# Aux_Lights_Daughter_REV3.net
KiCad netlist of a schematic drawn in Altium Designer
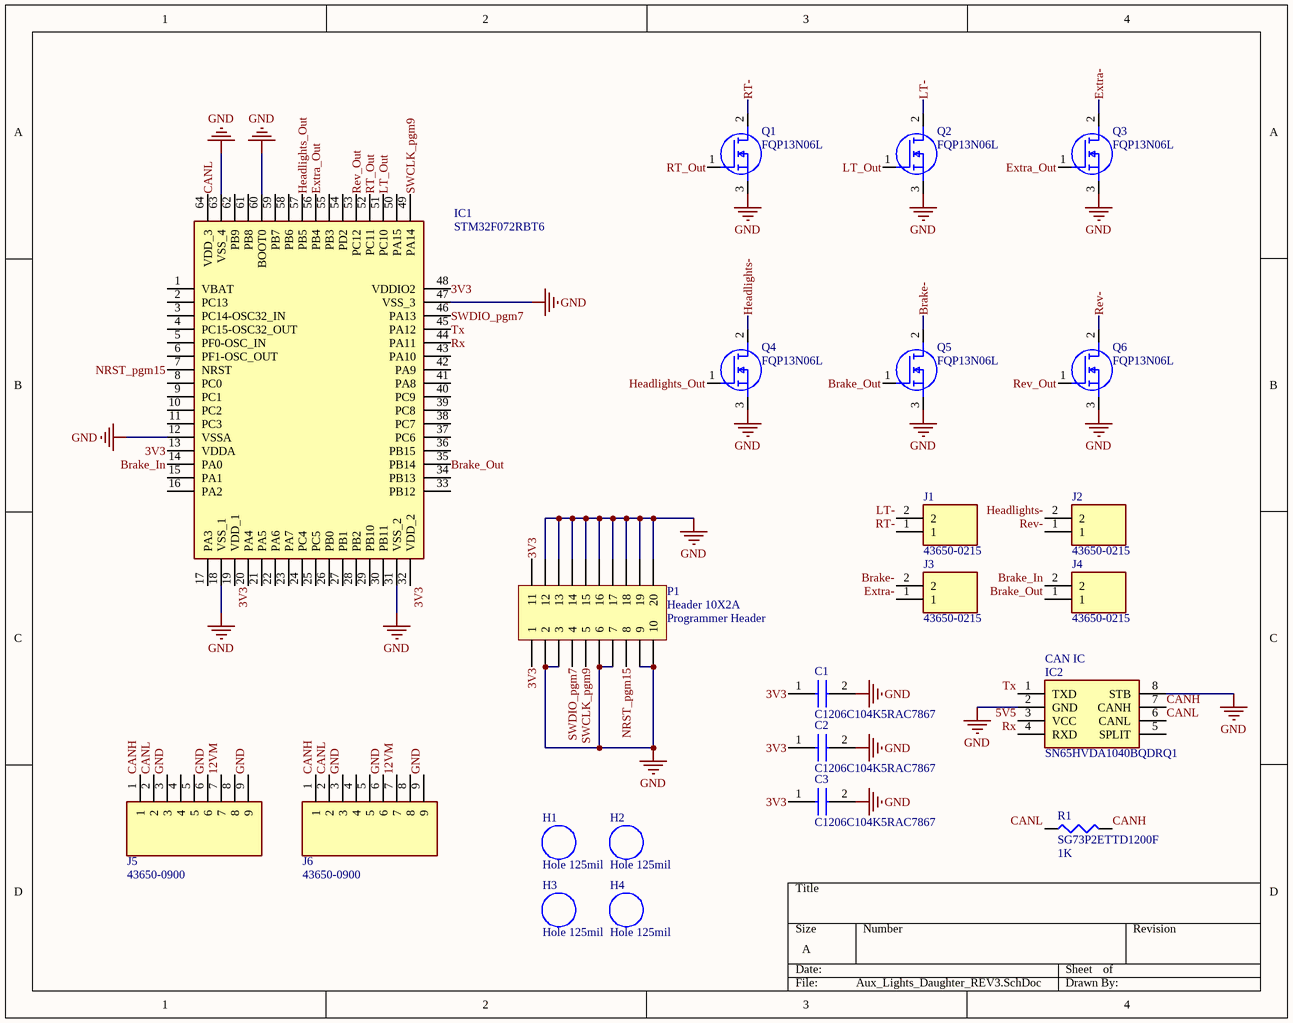
[diagram p0: Aux_Lights_Daughter_REV3.SchDoc]

(export (version "E")
  (design (tool "Eeschema 10.0.6"))
  (components
    (comp (ref "C1")
      (value "C1206C104K5RAC7867")
      (footprint "SG_Common:CAPC3216X110N")
      (description "Capacitor")
      (fields (field (name "MOUSER2 PART NUMBER") "80-C1206104K5RAC7867"))
      (libsource (lib "SG_Common") (part "C1206C104K5RAC7867"))
    )
    (comp (ref "C2")
      (value "C1206C104K5RAC7867")
      (footprint "SG_Common:CAPC3216X110N")
      (description "Capacitor")
      (fields (field (name "MOUSER2 PART NUMBER") "80-C1206104K5RAC7867"))
      (libsource (lib "SG_Common") (part "C1206C104K5RAC7867"))
    )
    (comp (ref "C3")
      (value "C1206C104K5RAC7867")
      (footprint "SG_Common:CAPC3216X110N")
      (description "Capacitor")
      (fields (field (name "MOUSER2 PART NUMBER") "80-C1206104K5RAC7867"))
      (libsource (lib "SG_Common") (part "C1206C104K5RAC7867"))
    )
    (comp (ref "H1")
      (value "Hole 125mil")
      (footprint "Hole")
      (libsource (lib "SG_Common") (part "Hole 125mil"))
    )
    (comp (ref "H2")
      (value "Hole 125mil")
      (footprint "Hole")
      (libsource (lib "SG_Common") (part "Hole 125mil"))
    )
    (comp (ref "H3")
      (value "Hole 125mil")
      (footprint "Hole")
      (libsource (lib "SG_Common") (part "Hole 125mil"))
    )
    (comp (ref "H4")
      (value "Hole 125mil")
      (footprint "Hole")
      (libsource (lib "SG_Common") (part "Hole 125mil"))
    )
    (comp (ref "IC1")
      (value "STM32F072RBT6")
      (footprint "SG_Common:QFP50P1200X1200X160-64N")
      (description "Integrated Circuit")
      (fields (field (name "MOUSER2 PART NUMBER") "511-STM32F072RBT6"))
      (libsource (lib "SG_Common") (part "STM32F072RBT6"))
    )
    (comp (ref "IC2")
      (value "SN65HVDA1040BQDRQ1")
      (footprint "SG_Common:SOIC127P600X175-8N")
      (description "Integrated Circuit")
      (libsource (lib "SG_Common") (part "SN65HVDA1040BQDRQ1"))
    )
    (comp (ref "J1")
      (value "43650-0215")
      (footprint "SG_Common:43650-02YY_15,16,17")
      (description "Connector")
      (fields (field (name "MOUSER2 PART NUMBER") "538-43650-0215"))
      (libsource (lib "SG_Common") (part "43650-0215"))
    )
    (comp (ref "J2")
      (value "43650-0215")
      (footprint "SG_Common:43650-02YY_15,16,17")
      (description "Connector")
      (fields (field (name "MOUSER2 PART NUMBER") "538-43650-0215"))
      (libsource (lib "SG_Common") (part "43650-0215"))
    )
    (comp (ref "J3")
      (value "43650-0215")
      (footprint "SG_Common:43650-02YY_15,16,17")
      (description "Connector")
      (fields (field (name "MOUSER2 PART NUMBER") "538-43650-0215"))
      (libsource (lib "SG_Common") (part "43650-0215"))
    )
    (comp (ref "J4")
      (value "43650-0215")
      (footprint "SG_Common:43650-02YY_15,16,17")
      (description "Connector")
      (fields (field (name "MOUSER2 PART NUMBER") "538-43650-0215"))
      (libsource (lib "SG_Common") (part "43650-0215"))
    )
    (comp (ref "J5")
      (value "43650-0900")
      (footprint "43650-09YY_R")
      (description "Connector")
      (libsource (lib "SG_Common") (part "43650-0900"))
    )
    (comp (ref "J6")
      (value "43650-0900")
      (footprint "43650-09YY_R")
      (description "Connector")
      (libsource (lib "SG_Common") (part "43650-0900"))
    )
    (comp (ref "P1")
      (value "Header 10X2A")
      (footprint "HDR2X10_CEN")
      (description "Header, 10-Pin, Dual row")
      (fields (field (name "PUBLISHER") "Altium Limited"))
      (libsource (lib "Miscellaneous Connectors") (part "Header 10X2A"))
    )
    (comp (ref "Q1")
      (value "FQP13N06L")
      (footprint "SG_Common:TO254P483X1016X2261-3P")
      (description "MOSFET (N-Channel)")
      (fields (field (name "MOUSER2 PART NUMBER") "512-FQP13N06L"))
      (libsource (lib "SG_Common") (part "FQP13N06L"))
    )
    (comp (ref "Q2")
      (value "FQP13N06L")
      (footprint "SG_Common:TO254P483X1016X2261-3P")
      (description "MOSFET (N-Channel)")
      (fields (field (name "MOUSER2 PART NUMBER") "512-FQP13N06L"))
      (libsource (lib "SG_Common") (part "FQP13N06L"))
    )
    (comp (ref "Q3")
      (value "FQP13N06L")
      (footprint "SG_Common:TO254P483X1016X2261-3P")
      (description "MOSFET (N-Channel)")
      (fields (field (name "MOUSER2 PART NUMBER") "512-FQP13N06L"))
      (libsource (lib "SG_Common") (part "FQP13N06L"))
    )
    (comp (ref "Q4")
      (value "FQP13N06L")
      (footprint "SG_Common:TO254P483X1016X2261-3P")
      (description "MOSFET (N-Channel)")
      (fields (field (name "MOUSER2 PART NUMBER") "512-FQP13N06L"))
      (libsource (lib "SG_Common") (part "FQP13N06L"))
    )
    (comp (ref "Q5")
      (value "FQP13N06L")
      (footprint "SG_Common:TO254P483X1016X2261-3P")
      (description "MOSFET (N-Channel)")
      (fields (field (name "MOUSER2 PART NUMBER") "512-FQP13N06L"))
      (libsource (lib "SG_Common") (part "FQP13N06L"))
    )
    (comp (ref "Q6")
      (value "FQP13N06L")
      (footprint "SG_Common:TO254P483X1016X2261-3P")
      (description "MOSFET (N-Channel)")
      (fields (field (name "MOUSER2 PART NUMBER") "512-FQP13N06L"))
      (libsource (lib "SG_Common") (part "FQP13N06L"))
    )
    (comp (ref "R1")
      (value "SG73P2ETTD1200F")
      (footprint "14-1210")
      (description "Resistor")
      (fields (field (name "ALTIUM_VALUE") "1K") (field (name "PUBLISHER") "Altium Limited"))
      (libsource (lib "Miscellaneous Devices") (part "Res3"))
    )
  )
  (nets
    (net (code "1") (name "/3V3") (class "Default")
      (node (ref "C1") (pin "1") (pinfunction "1_1") (pintype "passive"))
      (node (ref "C2") (pin "1") (pinfunction "1_1") (pintype "passive"))
      (node (ref "C3") (pin "1") (pinfunction "1_1") (pintype "passive"))
      (node (ref "IC1") (pin "13") (pinfunction "VDDA_13") (pintype "passive"))
      (node (ref "IC1") (pin "19") (pinfunction "VDD_1_19") (pintype "passive"))
      (node (ref "IC1") (pin "32") (pinfunction "VDD_2_32") (pintype "passive"))
      (node (ref "IC1") (pin "48") (pinfunction "VDDIO2_48") (pintype "passive"))
      (node (ref "P1") (pin "1") (pinfunction "1_1") (pintype "passive"))
      (node (ref "P1") (pin "11") (pinfunction "11_11") (pintype "passive"))
    )
    (net (code "2") (name "/5V5") (class "Default")
      (node (ref "IC2") (pin "3") (pinfunction "VCC_3") (pintype "passive"))
    )
    (net (code "3") (name "/12VM") (class "Default")
      (node (ref "J5") (pin "7") (pinfunction "7_7") (pintype "passive"))
      (node (ref "J6") (pin "7") (pinfunction "7_7") (pintype "passive"))
    )
    (net (code "4") (name "/Brake-") (class "Default")
      (node (ref "J3") (pin "2") (pinfunction "2_2") (pintype "passive"))
      (node (ref "Q5") (pin "2") (pinfunction "D_2") (pintype "passive"))
    )
    (net (code "5") (name "/Brake_In") (class "Default")
      (node (ref "IC1") (pin "14") (pinfunction "PA0_14") (pintype "passive"))
      (node (ref "J4") (pin "2") (pinfunction "2_2") (pintype "passive"))
    )
    (net (code "6") (name "/Brake_Out") (class "Default")
      (node (ref "IC1") (pin "35") (pinfunction "PB14_35") (pintype "passive"))
      (node (ref "J4") (pin "1") (pinfunction "1_1") (pintype "passive"))
      (node (ref "Q5") (pin "1") (pinfunction "G_1") (pintype "passive"))
    )
    (net (code "7") (name "/CANH") (class "Default")
      (node (ref "IC2") (pin "7") (pinfunction "CANH_7") (pintype "passive"))
      (node (ref "J5") (pin "1") (pinfunction "1_1") (pintype "passive"))
      (node (ref "J6") (pin "1") (pinfunction "1_1") (pintype "passive"))
      (node (ref "R1") (pin "2") (pinfunction "2_2") (pintype "passive"))
    )
    (net (code "8") (name "/CANL") (class "Default")
      (node (ref "IC1") (pin "64") (pinfunction "VDD_3_64") (pintype "passive"))
      (node (ref "IC2") (pin "6") (pinfunction "CANL_6") (pintype "passive"))
      (node (ref "J5") (pin "2") (pinfunction "2_2") (pintype "passive"))
      (node (ref "J6") (pin "2") (pinfunction "2_2") (pintype "passive"))
      (node (ref "R1") (pin "1") (pinfunction "1_1") (pintype "passive"))
    )
    (net (code "9") (name "/Extra-") (class "Default")
      (node (ref "J3") (pin "1") (pinfunction "1_1") (pintype "passive"))
      (node (ref "Q3") (pin "2") (pinfunction "D_2") (pintype "passive"))
    )
    (net (code "10") (name "/Extra_Out") (class "Default")
      (node (ref "IC1") (pin "56") (pinfunction "PB4_56") (pintype "passive"))
      (node (ref "Q3") (pin "1") (pinfunction "G_1") (pintype "passive"))
    )
    (net (code "11") (name "/Headlights-") (class "Default")
      (node (ref "J2") (pin "2") (pinfunction "2_2") (pintype "passive"))
      (node (ref "Q4") (pin "2") (pinfunction "D_2") (pintype "passive"))
    )
    (net (code "12") (name "/Headlights_Out") (class "Default")
      (node (ref "IC1") (pin "57") (pinfunction "PB5_57") (pintype "passive"))
      (node (ref "Q4") (pin "1") (pinfunction "G_1") (pintype "passive"))
    )
    (net (code "13") (name "/LT-") (class "Default")
      (node (ref "J1") (pin "2") (pinfunction "2_2") (pintype "passive"))
      (node (ref "Q2") (pin "2") (pinfunction "D_2") (pintype "passive"))
    )
    (net (code "14") (name "/LT_Out") (class "Default")
      (node (ref "IC1") (pin "51") (pinfunction "PC10_51") (pintype "passive"))
      (node (ref "Q2") (pin "1") (pinfunction "G_1") (pintype "passive"))
    )
    (net (code "15") (name "/NRST_pgm15") (class "Default")
      (node (ref "IC1") (pin "7") (pinfunction "NRST_7") (pintype "passive"))
      (node (ref "P1") (pin "8") (pinfunction "8_8") (pintype "passive"))
    )
    (net (code "16") (name "/RT-") (class "Default")
      (node (ref "J1") (pin "1") (pinfunction "1_1") (pintype "passive"))
      (node (ref "Q1") (pin "2") (pinfunction "D_2") (pintype "passive"))
    )
    (net (code "17") (name "/RT_Out") (class "Default")
      (node (ref "IC1") (pin "52") (pinfunction "PC11_52") (pintype "passive"))
      (node (ref "Q1") (pin "1") (pinfunction "G_1") (pintype "passive"))
    )
    (net (code "18") (name "/Rev-") (class "Default")
      (node (ref "J2") (pin "1") (pinfunction "1_1") (pintype "passive"))
      (node (ref "Q6") (pin "2") (pinfunction "D_2") (pintype "passive"))
    )
    (net (code "19") (name "/Rev_Out") (class "Default")
      (node (ref "IC1") (pin "53") (pinfunction "PC12_53") (pintype "passive"))
      (node (ref "Q6") (pin "1") (pinfunction "G_1") (pintype "passive"))
    )
    (net (code "20") (name "/Rx") (class "Default")
      (node (ref "IC1") (pin "44") (pinfunction "PA11_44") (pintype "passive"))
      (node (ref "IC2") (pin "4") (pinfunction "RXD_4") (pintype "passive"))
    )
    (net (code "21") (name "/SWCLK_pgm9") (class "Default")
      (node (ref "IC1") (pin "49") (pinfunction "PA14_49") (pintype "passive"))
      (node (ref "P1") (pin "5") (pinfunction "5_5") (pintype "passive"))
    )
    (net (code "22") (name "/SWDIO_pgm7") (class "Default")
      (node (ref "IC1") (pin "46") (pinfunction "PA13_46") (pintype "passive"))
      (node (ref "P1") (pin "4") (pinfunction "4_4") (pintype "passive"))
    )
    (net (code "23") (name "/Tx") (class "Default")
      (node (ref "IC1") (pin "45") (pinfunction "PA12_45") (pintype "passive"))
      (node (ref "IC2") (pin "1") (pinfunction "TXD_1") (pintype "passive"))
    )
    (net (code "24") (name "GND") (class "Default")
      (node (ref "C1") (pin "2") (pinfunction "2_2") (pintype "passive"))
      (node (ref "C2") (pin "2") (pinfunction "2_2") (pintype "passive"))
      (node (ref "C3") (pin "2") (pinfunction "2_2") (pintype "passive"))
      (node (ref "IC1") (pin "12") (pinfunction "VSSA_12") (pintype "passive"))
      (node (ref "IC1") (pin "18") (pinfunction "VSS_1_18") (pintype "passive"))
      (node (ref "IC1") (pin "31") (pinfunction "VSS_2_31") (pintype "passive"))
      (node (ref "IC1") (pin "47") (pinfunction "VSS_3_47") (pintype "passive"))
      (node (ref "IC1") (pin "60") (pinfunction "BOOT0_60") (pintype "passive"))
      (node (ref "IC1") (pin "63") (pinfunction "VSS_4_63") (pintype "passive"))
      (node (ref "IC2") (pin "2") (pinfunction "GND_2") (pintype "passive"))
      (node (ref "IC2") (pin "8") (pinfunction "STB_8") (pintype "passive"))
      (node (ref "J5") (pin "3") (pinfunction "3_3") (pintype "passive"))
      (node (ref "J5") (pin "6") (pinfunction "6_6") (pintype "passive"))
      (node (ref "J5") (pin "9") (pinfunction "9_9") (pintype "passive"))
      (node (ref "J6") (pin "3") (pinfunction "3_3") (pintype "passive"))
      (node (ref "J6") (pin "6") (pinfunction "6_6") (pintype "passive"))
      (node (ref "J6") (pin "9") (pinfunction "9_9") (pintype "passive"))
      (node (ref "P1") (pin "10") (pinfunction "10_10") (pintype "passive"))
      (node (ref "P1") (pin "12") (pinfunction "12_12") (pintype "passive"))
      (node (ref "P1") (pin "13") (pinfunction "13_13") (pintype "passive"))
      (node (ref "P1") (pin "14") (pinfunction "14_14") (pintype "passive"))
      (node (ref "P1") (pin "15") (pinfunction "15_15") (pintype "passive"))
      (node (ref "P1") (pin "16") (pinfunction "16_16") (pintype "passive"))
      (node (ref "P1") (pin "17") (pinfunction "17_17") (pintype "passive"))
      (node (ref "P1") (pin "18") (pinfunction "18_18") (pintype "passive"))
      (node (ref "P1") (pin "19") (pinfunction "19_19") (pintype "passive"))
      (node (ref "P1") (pin "2") (pinfunction "2_2") (pintype "passive"))
      (node (ref "P1") (pin "20") (pinfunction "20_20") (pintype "passive"))
      (node (ref "P1") (pin "3") (pinfunction "3_3") (pintype "passive"))
      (node (ref "P1") (pin "6") (pinfunction "6_6") (pintype "passive"))
      (node (ref "P1") (pin "7") (pinfunction "7_7") (pintype "passive"))
      (node (ref "P1") (pin "9") (pinfunction "9_9") (pintype "passive"))
      (node (ref "Q1") (pin "3") (pinfunction "S_3") (pintype "passive"))
      (node (ref "Q2") (pin "3") (pinfunction "S_3") (pintype "passive"))
      (node (ref "Q3") (pin "3") (pinfunction "S_3") (pintype "passive"))
      (node (ref "Q4") (pin "3") (pinfunction "S_3") (pintype "passive"))
      (node (ref "Q5") (pin "3") (pinfunction "S_3") (pintype "passive"))
      (node (ref "Q6") (pin "3") (pinfunction "S_3") (pintype "passive"))
    )
    (net (code "25") (name "unconnected-(IC1-PA1-Pad15)") (class "Default")
      (node (ref "IC1") (pin "15") (pinfunction "PA1_15") (pintype "passive"))
    )
    (net (code "26") (name "unconnected-(IC1-PA2-Pad16)") (class "Default")
      (node (ref "IC1") (pin "16") (pinfunction "PA2_16") (pintype "passive"))
    )
    (net (code "27") (name "unconnected-(IC1-PA3-Pad17)") (class "Default")
      (node (ref "IC1") (pin "17") (pinfunction "PA3_17") (pintype "passive"))
    )
    (net (code "28") (name "unconnected-(IC1-PA4-Pad20)") (class "Default")
      (node (ref "IC1") (pin "20") (pinfunction "PA4_20") (pintype "passive"))
    )
    (net (code "29") (name "unconnected-(IC1-PA5-Pad21)") (class "Default")
      (node (ref "IC1") (pin "21") (pinfunction "PA5_21") (pintype "passive"))
    )
    (net (code "30") (name "unconnected-(IC1-PA6-Pad22)") (class "Default")
      (node (ref "IC1") (pin "22") (pinfunction "PA6_22") (pintype "passive"))
    )
    (net (code "31") (name "unconnected-(IC1-PA7-Pad23)") (class "Default")
      (node (ref "IC1") (pin "23") (pinfunction "PA7_23") (pintype "passive"))
    )
    (net (code "32") (name "unconnected-(IC1-PA8-Pad41)") (class "Default")
      (node (ref "IC1") (pin "41") (pinfunction "PA8_41") (pintype "passive"))
    )
    (net (code "33") (name "unconnected-(IC1-PA9-Pad42)") (class "Default")
      (node (ref "IC1") (pin "42") (pinfunction "PA9_42") (pintype "passive"))
    )
    (net (code "34") (name "unconnected-(IC1-PA10-Pad43)") (class "Default")
      (node (ref "IC1") (pin "43") (pinfunction "PA10_43") (pintype "passive"))
    )
    (net (code "35") (name "unconnected-(IC1-PA15-Pad50)") (class "Default")
      (node (ref "IC1") (pin "50") (pinfunction "PA15_50") (pintype "passive"))
    )
    (net (code "36") (name "unconnected-(IC1-PB0-Pad26)") (class "Default")
      (node (ref "IC1") (pin "26") (pinfunction "PB0_26") (pintype "passive"))
    )
    (net (code "37") (name "unconnected-(IC1-PB1-Pad27)") (class "Default")
      (node (ref "IC1") (pin "27") (pinfunction "PB1_27") (pintype "passive"))
    )
    (net (code "38") (name "unconnected-(IC1-PB2-Pad28)") (class "Default")
      (node (ref "IC1") (pin "28") (pinfunction "PB2_28") (pintype "passive"))
    )
    (net (code "39") (name "unconnected-(IC1-PB3-Pad55)") (class "Default")
      (node (ref "IC1") (pin "55") (pinfunction "PB3_55") (pintype "passive"))
    )
    (net (code "40") (name "unconnected-(IC1-PB6-Pad58)") (class "Default")
      (node (ref "IC1") (pin "58") (pinfunction "PB6_58") (pintype "passive"))
    )
    (net (code "41") (name "unconnected-(IC1-PB7-Pad59)") (class "Default")
      (node (ref "IC1") (pin "59") (pinfunction "PB7_59") (pintype "passive"))
    )
    (net (code "42") (name "unconnected-(IC1-PB8-Pad61)") (class "Default")
      (node (ref "IC1") (pin "61") (pinfunction "PB8_61") (pintype "passive"))
    )
    (net (code "43") (name "unconnected-(IC1-PB9-Pad62)") (class "Default")
      (node (ref "IC1") (pin "62") (pinfunction "PB9_62") (pintype "passive"))
    )
    (net (code "44") (name "unconnected-(IC1-PB10-Pad29)") (class "Default")
      (node (ref "IC1") (pin "29") (pinfunction "PB10_29") (pintype "passive"))
    )
    (net (code "45") (name "unconnected-(IC1-PB11-Pad30)") (class "Default")
      (node (ref "IC1") (pin "30") (pinfunction "PB11_30") (pintype "passive"))
    )
    (net (code "46") (name "unconnected-(IC1-PB12-Pad33)") (class "Default")
      (node (ref "IC1") (pin "33") (pinfunction "PB12_33") (pintype "passive"))
    )
    (net (code "47") (name "unconnected-(IC1-PB13-Pad34)") (class "Default")
      (node (ref "IC1") (pin "34") (pinfunction "PB13_34") (pintype "passive"))
    )
    (net (code "48") (name "unconnected-(IC1-PB15-Pad36)") (class "Default")
      (node (ref "IC1") (pin "36") (pinfunction "PB15_36") (pintype "passive"))
    )
    (net (code "49") (name "unconnected-(IC1-PC0-Pad8)") (class "Default")
      (node (ref "IC1") (pin "8") (pinfunction "PC0_8") (pintype "passive"))
    )
    (net (code "50") (name "unconnected-(IC1-PC1-Pad9)") (class "Default")
      (node (ref "IC1") (pin "9") (pinfunction "PC1_9") (pintype "passive"))
    )
    (net (code "51") (name "unconnected-(IC1-PC2-Pad10)") (class "Default")
      (node (ref "IC1") (pin "10") (pinfunction "PC2_10") (pintype "passive"))
    )
    (net (code "52") (name "unconnected-(IC1-PC3-Pad11)") (class "Default")
      (node (ref "IC1") (pin "11") (pinfunction "PC3_11") (pintype "passive"))
    )
    (net (code "53") (name "unconnected-(IC1-PC4-Pad24)") (class "Default")
      (node (ref "IC1") (pin "24") (pinfunction "PC4_24") (pintype "passive"))
    )
    (net (code "54") (name "unconnected-(IC1-PC5-Pad25)") (class "Default")
      (node (ref "IC1") (pin "25") (pinfunction "PC5_25") (pintype "passive"))
    )
    (net (code "55") (name "unconnected-(IC1-PC6-Pad37)") (class "Default")
      (node (ref "IC1") (pin "37") (pinfunction "PC6_37") (pintype "passive"))
    )
    (net (code "56") (name "unconnected-(IC1-PC7-Pad38)") (class "Default")
      (node (ref "IC1") (pin "38") (pinfunction "PC7_38") (pintype "passive"))
    )
    (net (code "57") (name "unconnected-(IC1-PC8-Pad39)") (class "Default")
      (node (ref "IC1") (pin "39") (pinfunction "PC8_39") (pintype "passive"))
    )
    (net (code "58") (name "unconnected-(IC1-PC9-Pad40)") (class "Default")
      (node (ref "IC1") (pin "40") (pinfunction "PC9_40") (pintype "passive"))
    )
    (net (code "59") (name "unconnected-(IC1-PC13-Pad2)") (class "Default")
      (node (ref "IC1") (pin "2") (pinfunction "PC13_2") (pintype "passive"))
    )
    (net (code "60") (name "unconnected-(IC1-PC14-OSC32_IN-Pad3)") (class "Default")
      (node (ref "IC1") (pin "3") (pinfunction "PC14-OSC32_IN_3") (pintype "passive"))
    )
    (net (code "61") (name "unconnected-(IC1-PC15-OSC32_OUT-Pad4)") (class "Default")
      (node (ref "IC1") (pin "4") (pinfunction "PC15-OSC32_OUT_4") (pintype "passive"))
    )
    (net (code "62") (name "unconnected-(IC1-PD2-Pad54)") (class "Default")
      (node (ref "IC1") (pin "54") (pinfunction "PD2_54") (pintype "passive"))
    )
    (net (code "63") (name "unconnected-(IC1-PF0-OSC_IN-Pad5)") (class "Default")
      (node (ref "IC1") (pin "5") (pinfunction "PF0-OSC_IN_5") (pintype "passive"))
    )
    (net (code "64") (name "unconnected-(IC1-PF1-OSC_OUT-Pad6)") (class "Default")
      (node (ref "IC1") (pin "6") (pinfunction "PF1-OSC_OUT_6") (pintype "passive"))
    )
    (net (code "65") (name "unconnected-(IC1-VBAT-Pad1)") (class "Default")
      (node (ref "IC1") (pin "1") (pinfunction "VBAT_1") (pintype "passive"))
    )
    (net (code "66") (name "unconnected-(IC2-SPLIT-Pad5)") (class "Default")
      (node (ref "IC2") (pin "5") (pinfunction "SPLIT_5") (pintype "passive"))
    )
    (net (code "67") (name "unconnected-(J5-Pad4)") (class "Default")
      (node (ref "J5") (pin "4") (pinfunction "4_4") (pintype "passive"))
    )
    (net (code "68") (name "unconnected-(J5-Pad5)") (class "Default")
      (node (ref "J5") (pin "5") (pinfunction "5_5") (pintype "passive"))
    )
    (net (code "69") (name "unconnected-(J5-Pad8)") (class "Default")
      (node (ref "J5") (pin "8") (pinfunction "8_8") (pintype "passive"))
    )
    (net (code "70") (name "unconnected-(J6-Pad4)") (class "Default")
      (node (ref "J6") (pin "4") (pinfunction "4_4") (pintype "passive"))
    )
    (net (code "71") (name "unconnected-(J6-Pad5)") (class "Default")
      (node (ref "J6") (pin "5") (pinfunction "5_5") (pintype "passive"))
    )
    (net (code "72") (name "unconnected-(J6-Pad8)") (class "Default")
      (node (ref "J6") (pin "8") (pinfunction "8_8") (pintype "passive"))
    )
  )
)
